# BAI2.net
KiCad netlist of a schematic drawn in Altium Designer
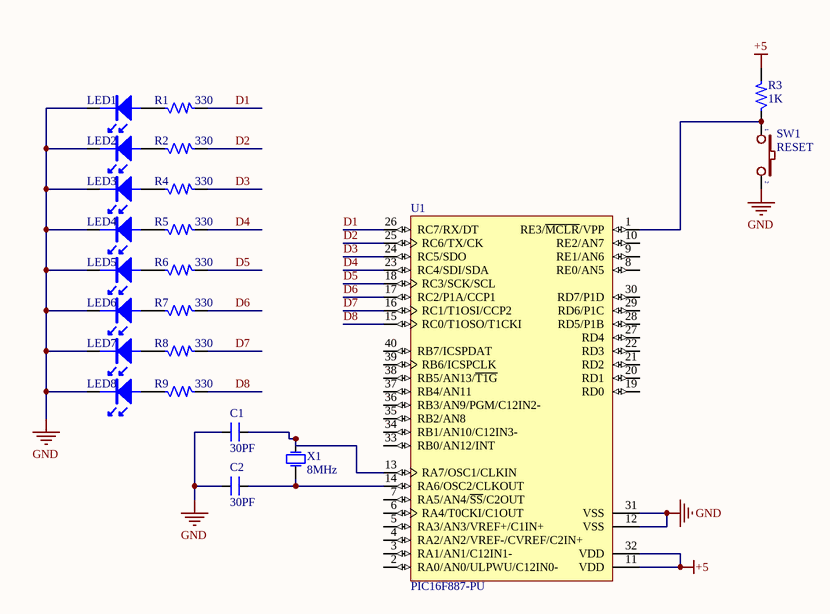
[diagram p0: BAI2.SchDoc]

(export (version "E")
  (design (tool "Eeschema 10.0.6"))
  (components
    (comp (ref "C1")
      (value "30PF")
      (footprint "SM-0805")
      (description "Cap SMD")
      (libsource (lib "Cty1") (part "CM"))
    )
    (comp (ref "C2")
      (value "30PF")
      (footprint "SM-0805")
      (description "Cap SMD")
      (libsource (lib "Cty1") (part "CM"))
    )
    (comp (ref "LED1") (value "LED") (footprint "CAP10UF") (libsource (lib "Cty1") (part "LED")))
    (comp (ref "LED2") (value "LED") (footprint "CAP10UF") (libsource (lib "Cty1") (part "LED")))
    (comp (ref "LED3") (value "LED") (footprint "CAP10UF") (libsource (lib "Cty1") (part "LED")))
    (comp (ref "LED4") (value "LED") (footprint "CAP10UF") (libsource (lib "Cty1") (part "LED")))
    (comp (ref "LED5") (value "LED") (footprint "CAP10UF") (libsource (lib "Cty1") (part "LED")))
    (comp (ref "LED6") (value "LED") (footprint "CAP10UF") (libsource (lib "Cty1") (part "LED")))
    (comp (ref "LED7") (value "LED") (footprint "CAP10UF") (libsource (lib "Cty1") (part "LED")))
    (comp (ref "LED8") (value "LED") (footprint "CAP10UF") (libsource (lib "Cty1") (part "LED")))
    (comp (ref "R1")
      (value "330")
      (footprint "R1/6W")
      (description "Resistor 1/4W")
      (libsource (lib "Cty1") (part "Res"))
    )
    (comp (ref "R2")
      (value "330")
      (footprint "R1/6W")
      (description "Resistor 1/4W")
      (libsource (lib "Cty1") (part "Res"))
    )
    (comp (ref "R3")
      (value "1K")
      (footprint "R1/6W")
      (description "Resistor 1/4W")
      (libsource (lib "Cty1") (part "Res"))
    )
    (comp (ref "R4")
      (value "330")
      (footprint "R1/6W")
      (description "Resistor 1/4W")
      (libsource (lib "Cty1") (part "Res"))
    )
    (comp (ref "R5")
      (value "330")
      (footprint "R1/6W")
      (description "Resistor 1/4W")
      (libsource (lib "Cty1") (part "Res"))
    )
    (comp (ref "R6")
      (value "330")
      (footprint "R1/6W")
      (description "Resistor 1/4W")
      (libsource (lib "Cty1") (part "Res"))
    )
    (comp (ref "R7")
      (value "330")
      (footprint "R1/6W")
      (description "Resistor 1/4W")
      (libsource (lib "Cty1") (part "Res"))
    )
    (comp (ref "R8")
      (value "330")
      (footprint "R1/6W")
      (description "Resistor 1/4W")
      (libsource (lib "Cty1") (part "Res"))
    )
    (comp (ref "R9")
      (value "330")
      (footprint "R1/6W")
      (description "Resistor 1/4W")
      (libsource (lib "Cty1") (part "Res"))
    )
    (comp (ref "SW1")
      (value "RESET")
      (footprint "SW2")
      (description "Switch button 2 pin")
      (libsource (lib "Cty1") (part "SW2"))
    )
    (comp (ref "U1")
      (value "PIC16F887-PU")
      (footprint "DIP40/W0.6")
      (fields (field (name "PUBLISHER") "Altium Limited"))
      (libsource (lib "My Library") (part "PIC16F887-PU"))
    )
    (comp (ref "X1")
      (value "8MHz")
      (footprint "XT2")
      (description "Crystal Oscillator")
      (fields (field (name "PUBLISHER") "Altium Limited"))
      (libsource (lib "Cty1") (part "Crystal"))
    )
  )
  (nets
    (net (code "1") (name "+5") (class "Default")
      (node (ref "R3") (pin "2") (pinfunction "2_2") (pintype "passive"))
      (node (ref "U1") (pin "11") (pinfunction "VDD_11") (pintype "power_in"))
      (node (ref "U1") (pin "32") (pinfunction "VDD_32") (pintype "power_in"))
    )
    (net (code "2") (name "/D1") (class "Default")
      (node (ref "R1") (pin "2") (pinfunction "2_2") (pintype "passive"))
      (node (ref "U1") (pin "26") (pinfunction "RC7/RX/DT_26") (pintype "bidirectional"))
    )
    (net (code "3") (name "/D2") (class "Default")
      (node (ref "R2") (pin "2") (pinfunction "2_2") (pintype "passive"))
      (node (ref "U1") (pin "25") (pinfunction "RC6/TX/CK_25") (pintype "bidirectional"))
    )
    (net (code "4") (name "/D3") (class "Default")
      (node (ref "R4") (pin "2") (pinfunction "2_2") (pintype "passive"))
      (node (ref "U1") (pin "24") (pinfunction "RC5/SDO_24") (pintype "bidirectional"))
    )
    (net (code "5") (name "/D4") (class "Default")
      (node (ref "R5") (pin "2") (pinfunction "2_2") (pintype "passive"))
      (node (ref "U1") (pin "23") (pinfunction "RC4/SDI/SDA_23") (pintype "bidirectional"))
    )
    (net (code "6") (name "/D5") (class "Default")
      (node (ref "R6") (pin "2") (pinfunction "2_2") (pintype "passive"))
      (node (ref "U1") (pin "18") (pinfunction "RC3/SCK/SCL_18") (pintype "bidirectional"))
    )
    (net (code "7") (name "/D6") (class "Default")
      (node (ref "R7") (pin "2") (pinfunction "2_2") (pintype "passive"))
      (node (ref "U1") (pin "17") (pinfunction "RC2/P1A/CCP1_17") (pintype "bidirectional"))
    )
    (net (code "8") (name "/D7") (class "Default")
      (node (ref "R8") (pin "2") (pinfunction "2_2") (pintype "passive"))
      (node (ref "U1") (pin "16") (pinfunction "RC1/T1OSI/CCP2_16") (pintype "bidirectional"))
    )
    (net (code "9") (name "/D8") (class "Default")
      (node (ref "R9") (pin "2") (pinfunction "2_2") (pintype "passive"))
      (node (ref "U1") (pin "15") (pinfunction "RC0/T1OSO/T1CKI_15") (pintype "bidirectional"))
    )
    (net (code "10") (name "GND") (class "Default")
      (node (ref "C1") (pin "1") (pinfunction "1_1") (pintype "passive"))
      (node (ref "C2") (pin "1") (pinfunction "1_1") (pintype "passive"))
      (node (ref "LED1") (pin "2") (pinfunction "2_2") (pintype "passive"))
      (node (ref "LED2") (pin "2") (pinfunction "2_2") (pintype "passive"))
      (node (ref "LED3") (pin "2") (pinfunction "2_2") (pintype "passive"))
      (node (ref "LED4") (pin "2") (pinfunction "2_2") (pintype "passive"))
      (node (ref "LED5") (pin "2") (pinfunction "2_2") (pintype "passive"))
      (node (ref "LED6") (pin "2") (pinfunction "2_2") (pintype "passive"))
      (node (ref "LED7") (pin "2") (pinfunction "2_2") (pintype "passive"))
      (node (ref "LED8") (pin "2") (pinfunction "2_2") (pintype "passive"))
      (node (ref "SW1") (pin "2") (pinfunction "2_2") (pintype "passive"))
      (node (ref "U1") (pin "12") (pinfunction "VSS_12") (pintype "power_in"))
      (node (ref "U1") (pin "31") (pinfunction "VSS_31") (pintype "power_in"))
    )
    (net (code "11") (name "Net-(LED1-Pad1)") (class "Default")
      (node (ref "LED1") (pin "1") (pinfunction "1_1") (pintype "passive"))
      (node (ref "R1") (pin "1") (pinfunction "1_1") (pintype "passive"))
    )
    (net (code "12") (name "Net-(LED2-Pad1)") (class "Default")
      (node (ref "LED2") (pin "1") (pinfunction "1_1") (pintype "passive"))
      (node (ref "R2") (pin "1") (pinfunction "1_1") (pintype "passive"))
    )
    (net (code "13") (name "Net-(LED3-Pad1)") (class "Default")
      (node (ref "LED3") (pin "1") (pinfunction "1_1") (pintype "passive"))
      (node (ref "R4") (pin "1") (pinfunction "1_1") (pintype "passive"))
    )
    (net (code "14") (name "Net-(LED4-Pad1)") (class "Default")
      (node (ref "LED4") (pin "1") (pinfunction "1_1") (pintype "passive"))
      (node (ref "R5") (pin "1") (pinfunction "1_1") (pintype "passive"))
    )
    (net (code "15") (name "Net-(LED5-Pad1)") (class "Default")
      (node (ref "LED5") (pin "1") (pinfunction "1_1") (pintype "passive"))
      (node (ref "R6") (pin "1") (pinfunction "1_1") (pintype "passive"))
    )
    (net (code "16") (name "Net-(LED6-Pad1)") (class "Default")
      (node (ref "LED6") (pin "1") (pinfunction "1_1") (pintype "passive"))
      (node (ref "R7") (pin "1") (pinfunction "1_1") (pintype "passive"))
    )
    (net (code "17") (name "Net-(LED7-Pad1)") (class "Default")
      (node (ref "LED7") (pin "1") (pinfunction "1_1") (pintype "passive"))
      (node (ref "R8") (pin "1") (pinfunction "1_1") (pintype "passive"))
    )
    (net (code "18") (name "Net-(LED8-Pad1)") (class "Default")
      (node (ref "LED8") (pin "1") (pinfunction "1_1") (pintype "passive"))
      (node (ref "R9") (pin "1") (pinfunction "1_1") (pintype "passive"))
    )
    (net (code "19") (name "Net-(U1-RA6{slash}OSC2{slash}CLKOUT)") (class "Default")
      (node (ref "C2") (pin "2") (pinfunction "2_2") (pintype "passive"))
      (node (ref "U1") (pin "14") (pinfunction "RA6/OSC2/CLKOUT_14") (pintype "bidirectional"))
      (node (ref "X1") (pin "1") (pinfunction "OSC1_1") (pintype "passive"))
    )
    (net (code "20") (name "Net-(U1-RA7{slash}OSC1{slash}CLKIN)") (class "Default")
      (node (ref "C1") (pin "2") (pinfunction "2_2") (pintype "passive"))
      (node (ref "U1") (pin "13") (pinfunction "RA7/OSC1/CLKIN_13") (pintype "bidirectional"))
      (node (ref "X1") (pin "2") (pinfunction "OSC2_2") (pintype "passive"))
    )
    (net (code "21") (name "Net-(U1-RE3{slash}~{MCLR}{slash}VPP)") (class "Default")
      (node (ref "R3") (pin "1") (pinfunction "1_1") (pintype "passive"))
      (node (ref "SW1") (pin "1") (pinfunction "1_1") (pintype "passive"))
      (node (ref "U1") (pin "1") (pinfunction "RE3/~{MCLR}/VPP_1") (pintype "bidirectional"))
    )
    (net (code "22") (name "unconnected-(U1-RA0{slash}AN0{slash}ULPWU{slash}C12IN0--Pad2)") (class "Default")
      (node (ref "U1") (pin "2") (pinfunction "RA0/AN0/ULPWU/C12IN0-_2") (pintype "bidirectional"))
    )
    (net (code "23") (name "unconnected-(U1-RA1{slash}AN1{slash}C12IN1--Pad3)") (class "Default")
      (node (ref "U1") (pin "3") (pinfunction "RA1/AN1/C12IN1-_3") (pintype "bidirectional"))
    )
    (net (code "24") (name "unconnected-(U1-RA2{slash}AN2{slash}VREF-{slash}CVREF{slash}C2IN+-Pad4)") (class "Default")
      (node (ref "U1") (pin "4") (pinfunction "RA2/AN2/VREF-/CVREF/C2IN+_4") (pintype "bidirectional"))
    )
    (net (code "25") (name "unconnected-(U1-RA3{slash}AN3{slash}VREF+{slash}C1IN+-Pad5)") (class "Default")
      (node (ref "U1") (pin "5") (pinfunction "RA3/AN3/VREF+/C1IN+_5") (pintype "bidirectional"))
    )
    (net (code "26") (name "unconnected-(U1-RA4{slash}T0CKI{slash}C1OUT-Pad6)") (class "Default")
      (node (ref "U1") (pin "6") (pinfunction "RA4/T0CKI/C1OUT_6") (pintype "bidirectional"))
    )
    (net (code "27") (name "unconnected-(U1-RA5{slash}AN4{slash}~{SS}{slash}C2OUT-Pad7)") (class "Default")
      (node (ref "U1") (pin "7") (pinfunction "RA5/AN4/~{SS}/C2OUT_7") (pintype "bidirectional"))
    )
    (net (code "28") (name "unconnected-(U1-RB0{slash}AN12{slash}INT-Pad33)") (class "Default")
      (node (ref "U1") (pin "33") (pinfunction "RB0/AN12/INT_33") (pintype "bidirectional"))
    )
    (net (code "29") (name "unconnected-(U1-RB1{slash}AN10{slash}C12IN3--Pad34)") (class "Default")
      (node (ref "U1") (pin "34") (pinfunction "RB1/AN10/C12IN3-_34") (pintype "bidirectional"))
    )
    (net (code "30") (name "unconnected-(U1-RB2{slash}AN8-Pad35)") (class "Default")
      (node (ref "U1") (pin "35") (pinfunction "RB2/AN8_35") (pintype "bidirectional"))
    )
    (net (code "31") (name "unconnected-(U1-RB3{slash}AN9{slash}PGM{slash}C12IN2--Pad36)") (class "Default")
      (node (ref "U1") (pin "36") (pinfunction "RB3/AN9/PGM/C12IN2-_36") (pintype "bidirectional"))
    )
    (net (code "32") (name "unconnected-(U1-RB4{slash}AN11-Pad37)") (class "Default")
      (node (ref "U1") (pin "37") (pinfunction "RB4/AN11_37") (pintype "bidirectional"))
    )
    (net (code "33") (name "unconnected-(U1-RB5{slash}AN13{slash}~{T1G}-Pad38)") (class "Default")
      (node (ref "U1") (pin "38") (pinfunction "RB5/AN13/~{T1G}_38") (pintype "bidirectional"))
    )
    (net (code "34") (name "unconnected-(U1-RB6{slash}ICSPCLK-Pad39)") (class "Default")
      (node (ref "U1") (pin "39") (pinfunction "RB6/ICSPCLK_39") (pintype "bidirectional"))
    )
    (net (code "35") (name "unconnected-(U1-RB7{slash}ICSPDAT-Pad40)") (class "Default")
      (node (ref "U1") (pin "40") (pinfunction "RB7/ICSPDAT_40") (pintype "bidirectional"))
    )
    (net (code "36") (name "unconnected-(U1-RD0-Pad19)") (class "Default")
      (node (ref "U1") (pin "19") (pinfunction "RD0_19") (pintype "bidirectional"))
    )
    (net (code "37") (name "unconnected-(U1-RD1-Pad20)") (class "Default")
      (node (ref "U1") (pin "20") (pinfunction "RD1_20") (pintype "bidirectional"))
    )
    (net (code "38") (name "unconnected-(U1-RD2-Pad21)") (class "Default")
      (node (ref "U1") (pin "21") (pinfunction "RD2_21") (pintype "bidirectional"))
    )
    (net (code "39") (name "unconnected-(U1-RD3-Pad22)") (class "Default")
      (node (ref "U1") (pin "22") (pinfunction "RD3_22") (pintype "bidirectional"))
    )
    (net (code "40") (name "unconnected-(U1-RD4-Pad27)") (class "Default")
      (node (ref "U1") (pin "27") (pinfunction "RD4_27") (pintype "bidirectional"))
    )
    (net (code "41") (name "unconnected-(U1-RD5{slash}P1B-Pad28)") (class "Default")
      (node (ref "U1") (pin "28") (pinfunction "RD5/P1B_28") (pintype "bidirectional"))
    )
    (net (code "42") (name "unconnected-(U1-RD6{slash}P1C-Pad29)") (class "Default")
      (node (ref "U1") (pin "29") (pinfunction "RD6/P1C_29") (pintype "bidirectional"))
    )
    (net (code "43") (name "unconnected-(U1-RD7{slash}P1D-Pad30)") (class "Default")
      (node (ref "U1") (pin "30") (pinfunction "RD7/P1D_30") (pintype "bidirectional"))
    )
    (net (code "44") (name "unconnected-(U1-RE0{slash}AN5-Pad8)") (class "Default")
      (node (ref "U1") (pin "8") (pinfunction "RE0/AN5_8") (pintype "bidirectional"))
    )
    (net (code "45") (name "unconnected-(U1-RE1{slash}AN6-Pad9)") (class "Default")
      (node (ref "U1") (pin "9") (pinfunction "RE1/AN6_9") (pintype "bidirectional"))
    )
    (net (code "46") (name "unconnected-(U1-RE2{slash}AN7-Pad10)") (class "Default")
      (node (ref "U1") (pin "10") (pinfunction "RE2/AN7_10") (pintype "bidirectional"))
    )
  )
)
